# ADC.net
KiCad netlist of a schematic drawn in Altium Designer
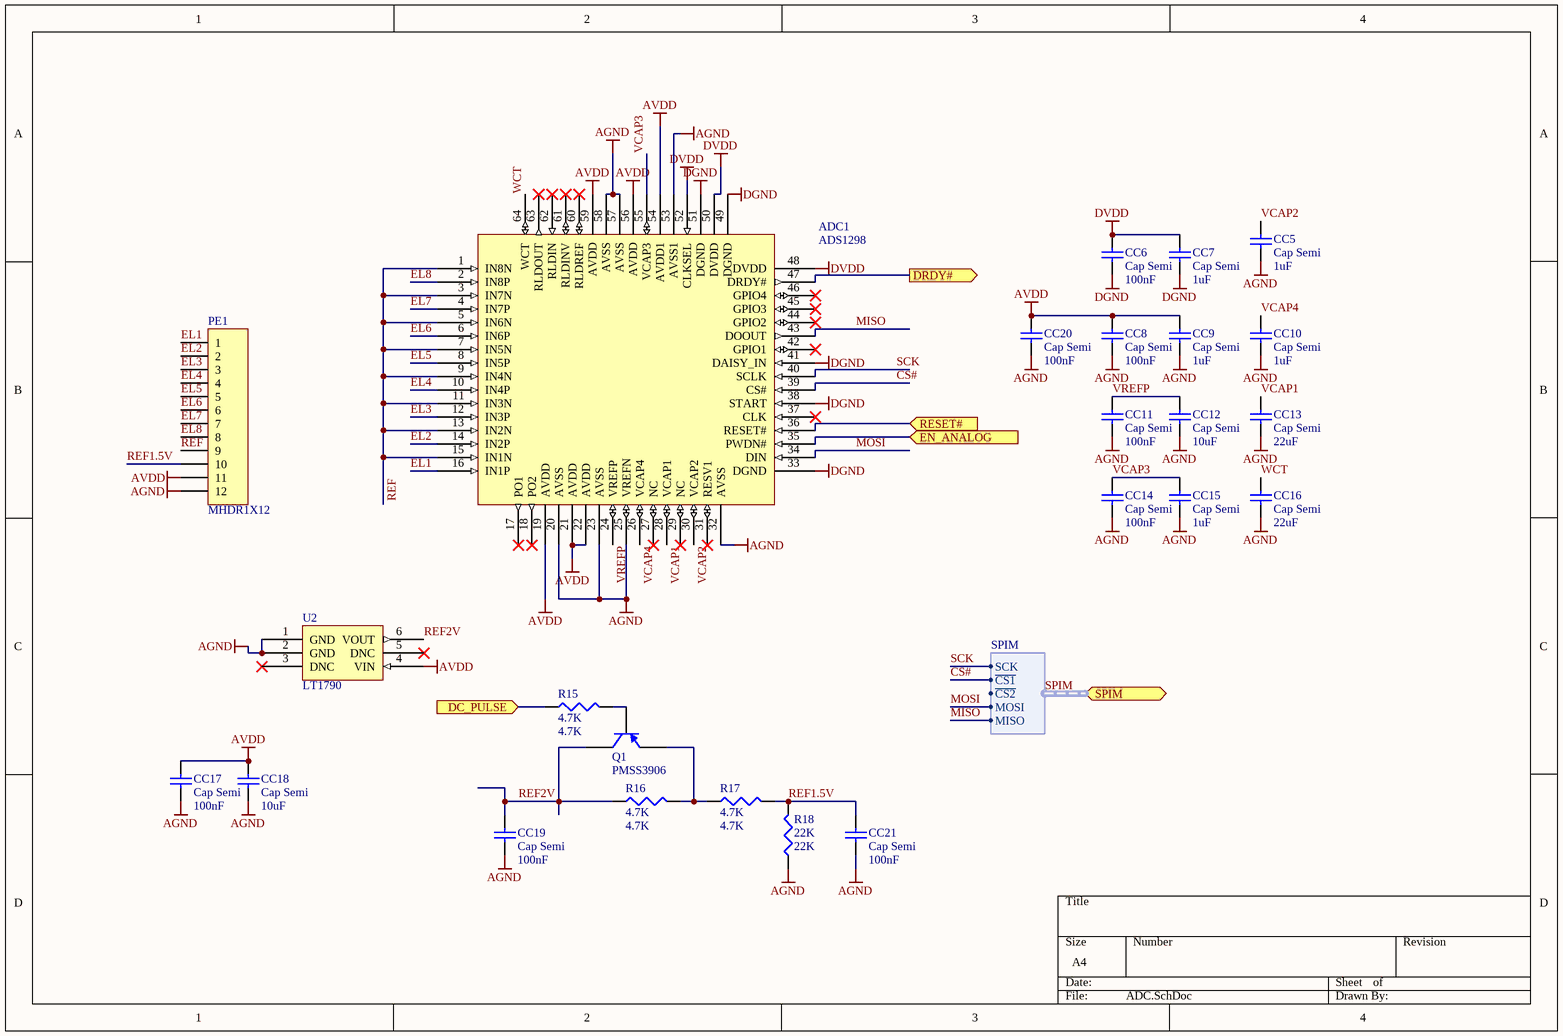
[diagram p0: ADC.SchDoc]

(export (version "E")
  (design (tool "Eeschema 10.0.6"))
  (components
    (comp (ref "ADC1")
      (value "ADS1298")
      (footprint "Atmel Microcontroller 32-Bit ARM:LQFP64_M")
      (libsource (lib "Schlib1") (part "ADS1298"))
    )
    (comp (ref "CC5")
      (value "Cap Semi")
      (footprint "0402")
      (description "Capacitor (Semiconductor SIM Model)")
      (fields (field (name "ALTIUM_VALUE") "1uF") (field (name "PUBLISHER") "Altium Limited"))
      (libsource (lib "Miscellaneous Devices") (part "Cap Semi"))
    )
    (comp (ref "CC6")
      (value "Cap Semi")
      (footprint "0402")
      (description "Capacitor (Semiconductor SIM Model)")
      (fields (field (name "ALTIUM_VALUE") "100nF") (field (name "PUBLISHER") "Altium Limited"))
      (libsource (lib "Miscellaneous Devices") (part "Cap Semi"))
    )
    (comp (ref "CC7")
      (value "Cap Semi")
      (footprint "0402")
      (description "Capacitor (Semiconductor SIM Model)")
      (fields (field (name "ALTIUM_VALUE") "1uF") (field (name "PUBLISHER") "Altium Limited"))
      (libsource (lib "Miscellaneous Devices") (part "Cap Semi"))
    )
    (comp (ref "CC8")
      (value "Cap Semi")
      (footprint "0402")
      (description "Capacitor (Semiconductor SIM Model)")
      (fields (field (name "ALTIUM_VALUE") "100nF") (field (name "PUBLISHER") "Altium Limited"))
      (libsource (lib "Miscellaneous Devices") (part "Cap Semi"))
    )
    (comp (ref "CC9")
      (value "Cap Semi")
      (footprint "0402")
      (description "Capacitor (Semiconductor SIM Model)")
      (fields (field (name "ALTIUM_VALUE") "1uF") (field (name "PUBLISHER") "Altium Limited"))
      (libsource (lib "Miscellaneous Devices") (part "Cap Semi"))
    )
    (comp (ref "CC10")
      (value "Cap Semi")
      (footprint "0402")
      (description "Capacitor (Semiconductor SIM Model)")
      (fields (field (name "ALTIUM_VALUE") "1uF") (field (name "PUBLISHER") "Altium Limited"))
      (libsource (lib "Miscellaneous Devices") (part "Cap Semi"))
    )
    (comp (ref "CC11")
      (value "Cap Semi")
      (footprint "0402")
      (description "Capacitor (Semiconductor SIM Model)")
      (fields (field (name "ALTIUM_VALUE") "100nF") (field (name "PUBLISHER") "Altium Limited"))
      (libsource (lib "Miscellaneous Devices") (part "Cap Semi"))
    )
    (comp (ref "CC12")
      (value "Cap Semi")
      (footprint "0402")
      (description "Capacitor (Semiconductor SIM Model)")
      (fields (field (name "ALTIUM_VALUE") "10uF") (field (name "PUBLISHER") "Altium Limited"))
      (libsource (lib "Miscellaneous Devices") (part "Cap Semi"))
    )
    (comp (ref "CC13")
      (value "Cap Semi")
      (footprint "0402")
      (description "Capacitor (Semiconductor SIM Model)")
      (fields (field (name "ALTIUM_VALUE") "22uF") (field (name "PUBLISHER") "Altium Limited"))
      (libsource (lib "Miscellaneous Devices") (part "Cap Semi"))
    )
    (comp (ref "CC14")
      (value "Cap Semi")
      (footprint "0402")
      (description "Capacitor (Semiconductor SIM Model)")
      (fields (field (name "ALTIUM_VALUE") "100nF") (field (name "PUBLISHER") "Altium Limited"))
      (libsource (lib "Miscellaneous Devices") (part "Cap Semi"))
    )
    (comp (ref "CC15")
      (value "Cap Semi")
      (footprint "0402")
      (description "Capacitor (Semiconductor SIM Model)")
      (fields (field (name "ALTIUM_VALUE") "1uF") (field (name "PUBLISHER") "Altium Limited"))
      (libsource (lib "Miscellaneous Devices") (part "Cap Semi"))
    )
    (comp (ref "CC16")
      (value "Cap Semi")
      (footprint "1608[0603]")
      (description "Capacitor (Semiconductor SIM Model)")
      (fields (field (name "ALTIUM_VALUE") "22uF") (field (name "PUBLISHER") "Altium Limited"))
      (libsource (lib "Miscellaneous Devices") (part "Cap Semi"))
    )
    (comp (ref "CC17")
      (value "Cap Semi")
      (footprint "0402")
      (description "Capacitor (Semiconductor SIM Model)")
      (fields (field (name "ALTIUM_VALUE") "100nF") (field (name "PUBLISHER") "Altium Limited"))
      (libsource (lib "Miscellaneous Devices") (part "Cap Semi"))
    )
    (comp (ref "CC18")
      (value "Cap Semi")
      (footprint "0402")
      (description "Capacitor (Semiconductor SIM Model)")
      (fields (field (name "ALTIUM_VALUE") "10uF") (field (name "PUBLISHER") "Altium Limited"))
      (libsource (lib "Miscellaneous Devices") (part "Cap Semi"))
    )
    (comp (ref "CC19")
      (value "Cap Semi")
      (footprint "0402")
      (description "Capacitor (Semiconductor SIM Model)")
      (fields (field (name "ALTIUM_VALUE") "100nF") (field (name "PUBLISHER") "Altium Limited"))
      (libsource (lib "Miscellaneous Devices") (part "Cap Semi"))
    )
    (comp (ref "CC20")
      (value "Cap Semi")
      (footprint "0402")
      (description "Capacitor (Semiconductor SIM Model)")
      (fields (field (name "ALTIUM_VALUE") "100nF") (field (name "PUBLISHER") "Altium Limited"))
      (libsource (lib "Miscellaneous Devices") (part "Cap Semi"))
    )
    (comp (ref "CC21")
      (value "Cap Semi")
      (footprint "0402")
      (description "Capacitor (Semiconductor SIM Model)")
      (fields (field (name "ALTIUM_VALUE") "100nF") (field (name "PUBLISHER") "Altium Limited"))
      (libsource (lib "Miscellaneous Devices") (part "Cap Semi"))
    )
    (comp (ref "PE1")
      (value "MHDR1X12")
      (footprint "HEADER12")
      (description "Header, 12-Pin")
      (fields (field (name "PUBLISHER") "Altium Limited"))
      (libsource (lib "Miscellaneous Connectors") (part "MHDR1X12"))
    )
    (comp (ref "Q1")
      (value "PMSS3906")
      (footprint "SOT323_N")
      (description "PNP Switching Transistor")
      (fields (field (name "PUBLISHER") "Altium Limited"))
      (libsource (lib "Philips Discrete BJT - Low Power") (part "PMSS3906"))
    )
    (comp (ref "R15")
      (value "4.7K")
      (footprint "0402")
      (description "Resistor")
      (fields (field (name "ALTIUM_VALUE") "4.7K") (field (name "PUBLISHER") "Altium Limited"))
      (libsource (lib "Miscellaneous Devices") (part "Res3"))
    )
    (comp (ref "R16")
      (value "4.7K")
      (footprint "0402")
      (description "Resistor")
      (fields (field (name "ALTIUM_VALUE") "4.7K") (field (name "PUBLISHER") "Altium Limited"))
      (libsource (lib "Miscellaneous Devices") (part "Res3"))
    )
    (comp (ref "R17")
      (value "4.7K")
      (footprint "0402")
      (description "Resistor")
      (fields (field (name "ALTIUM_VALUE") "4.7K") (field (name "PUBLISHER") "Altium Limited"))
      (libsource (lib "Miscellaneous Devices") (part "Res3"))
    )
    (comp (ref "R18")
      (value "22K")
      (footprint "0402")
      (description "Resistor")
      (fields (field (name "ALTIUM_VALUE") "22K") (field (name "PUBLISHER") "Altium Limited"))
      (libsource (lib "Miscellaneous Devices") (part "Res3"))
    )
    (comp (ref "U2") (value "LT1790") (footprint "SOT-23_A_N") (libsource (lib "Schlib1") (part "LT1790")))
  )
  (nets
    (net (code "2") (name "/CS#") (class "Default")
      (node (ref "ADC1") (pin "39") (pinfunction "CS#_39") (pintype "input"))
    )
    (net (code "3") (name "/DC_PULSE") (class "Default")
      (node (ref "R15") (pin "1") (pinfunction "1_1") (pintype "passive"))
    )
    (net (code "4") (name "/DRDY#") (class "Default")
      (node (ref "ADC1") (pin "47") (pinfunction "DRDY#_47") (pintype "output"))
    )
    (net (code "5") (name "/EL1") (class "Default")
      (node (ref "ADC1") (pin "16") (pinfunction "IN1P_16") (pintype "input"))
      (node (ref "PE1") (pin "1") (pinfunction "1_1") (pintype "passive"))
    )
    (net (code "6") (name "/EL2") (class "Default")
      (node (ref "ADC1") (pin "14") (pinfunction "IN2P_14") (pintype "input"))
      (node (ref "PE1") (pin "2") (pinfunction "2_2") (pintype "passive"))
    )
    (net (code "7") (name "/EL3") (class "Default")
      (node (ref "ADC1") (pin "12") (pinfunction "IN3P_12") (pintype "input"))
      (node (ref "PE1") (pin "3") (pinfunction "3_3") (pintype "passive"))
    )
    (net (code "8") (name "/EL4") (class "Default")
      (node (ref "ADC1") (pin "10") (pinfunction "IN4P_10") (pintype "input"))
      (node (ref "PE1") (pin "4") (pinfunction "4_4") (pintype "passive"))
    )
    (net (code "9") (name "/EL5") (class "Default")
      (node (ref "ADC1") (pin "8") (pinfunction "IN5P_8") (pintype "input"))
      (node (ref "PE1") (pin "5") (pinfunction "5_5") (pintype "passive"))
    )
    (net (code "10") (name "/EL6") (class "Default")
      (node (ref "ADC1") (pin "6") (pinfunction "IN6P_6") (pintype "input"))
      (node (ref "PE1") (pin "6") (pinfunction "6_6") (pintype "passive"))
    )
    (net (code "11") (name "/EL7") (class "Default")
      (node (ref "ADC1") (pin "4") (pinfunction "IN7P_4") (pintype "input"))
      (node (ref "PE1") (pin "7") (pinfunction "7_7") (pintype "passive"))
    )
    (net (code "12") (name "/EL8") (class "Default")
      (node (ref "ADC1") (pin "2") (pinfunction "IN8P_2") (pintype "input"))
      (node (ref "PE1") (pin "8") (pinfunction "8_8") (pintype "passive"))
    )
    (net (code "13") (name "/EN_ANALOG") (class "Default")
      (node (ref "ADC1") (pin "35") (pinfunction "PWDN#_35") (pintype "input"))
    )
    (net (code "14") (name "/MISO") (class "Default")
      (node (ref "ADC1") (pin "43") (pinfunction "DOOUT_43") (pintype "output"))
    )
    (net (code "15") (name "/MOSI") (class "Default")
      (node (ref "ADC1") (pin "34") (pinfunction "DIN_34") (pintype "input"))
    )
    (net (code "16") (name "/REF") (class "Default")
      (node (ref "ADC1") (pin "1") (pinfunction "IN8N_1") (pintype "input"))
      (node (ref "ADC1") (pin "11") (pinfunction "IN3N_11") (pintype "input"))
      (node (ref "ADC1") (pin "13") (pinfunction "IN2N_13") (pintype "input"))
      (node (ref "ADC1") (pin "15") (pinfunction "IN1N_15") (pintype "input"))
      (node (ref "ADC1") (pin "3") (pinfunction "IN7N_3") (pintype "input"))
      (node (ref "ADC1") (pin "5") (pinfunction "IN6N_5") (pintype "input"))
      (node (ref "ADC1") (pin "7") (pinfunction "IN5N_7") (pintype "input"))
      (node (ref "ADC1") (pin "9") (pinfunction "IN4N_9") (pintype "input"))
      (node (ref "PE1") (pin "9") (pinfunction "9_9") (pintype "passive"))
    )
    (net (code "17") (name "/REF1.5V") (class "Default")
      (node (ref "CC21") (pin "2") (pinfunction "2_2") (pintype "passive"))
      (node (ref "PE1") (pin "10") (pinfunction "10_10") (pintype "passive"))
      (node (ref "R17") (pin "2") (pinfunction "2_2") (pintype "passive"))
      (node (ref "R18") (pin "2") (pinfunction "2_2") (pintype "passive"))
    )
    (net (code "18") (name "/REF2V") (class "Default")
      (node (ref "CC19") (pin "2") (pinfunction "2_2") (pintype "passive"))
      (node (ref "Q1") (pin "3") (pinfunction "C_3") (pintype "passive"))
      (node (ref "R16") (pin "1") (pinfunction "1_1") (pintype "passive"))
      (node (ref "U2") (pin "6") (pinfunction "VOUT_6") (pintype "output"))
    )
    (net (code "19") (name "/RESET#") (class "Default")
      (node (ref "ADC1") (pin "36") (pinfunction "RESET#_36") (pintype "input"))
    )
    (net (code "20") (name "/SCK") (class "Default")
      (node (ref "ADC1") (pin "40") (pinfunction "SCLK_40") (pintype "input"))
    )
    (net (code "22") (name "/VCAP1") (class "Default")
      (node (ref "ADC1") (pin "28") (pinfunction "VCAP1_28") (pintype "bidirectional"))
      (node (ref "CC13") (pin "2") (pinfunction "2_2") (pintype "passive"))
    )
    (net (code "23") (name "/VCAP2") (class "Default")
      (node (ref "ADC1") (pin "30") (pinfunction "VCAP2_30") (pintype "bidirectional"))
      (node (ref "CC5") (pin "2") (pinfunction "2_2") (pintype "passive"))
    )
    (net (code "24") (name "/VCAP3") (class "Default")
      (node (ref "ADC1") (pin "55") (pinfunction "VCAP3_55") (pintype "bidirectional"))
      (node (ref "CC14") (pin "2") (pinfunction "2_2") (pintype "passive"))
      (node (ref "CC15") (pin "2") (pinfunction "2_2") (pintype "passive"))
    )
    (net (code "25") (name "/VCAP4") (class "Default")
      (node (ref "ADC1") (pin "26") (pinfunction "VCAP4_26") (pintype "bidirectional"))
      (node (ref "CC10") (pin "2") (pinfunction "2_2") (pintype "passive"))
    )
    (net (code "26") (name "/VREFP") (class "Default")
      (node (ref "ADC1") (pin "24") (pinfunction "VREFP_24") (pintype "bidirectional"))
      (node (ref "CC11") (pin "2") (pinfunction "2_2") (pintype "passive"))
      (node (ref "CC12") (pin "2") (pinfunction "2_2") (pintype "passive"))
    )
    (net (code "27") (name "/WCT") (class "Default")
      (node (ref "ADC1") (pin "64") (pinfunction "WCT_64") (pintype "bidirectional"))
      (node (ref "CC16") (pin "2") (pinfunction "2_2") (pintype "passive"))
    )
    (net (code "28") (name "AGND") (class "Default")
      (node (ref "ADC1") (pin "20") (pinfunction "AVSS_20") (pintype "power_in"))
      (node (ref "ADC1") (pin "23") (pinfunction "AVSS_23") (pintype "power_in"))
      (node (ref "ADC1") (pin "25") (pinfunction "VREFN_25") (pintype "bidirectional"))
      (node (ref "ADC1") (pin "32") (pinfunction "AVSS_32") (pintype "power_in"))
      (node (ref "ADC1") (pin "53") (pinfunction "AVSS1_53") (pintype "power_in"))
      (node (ref "ADC1") (pin "57") (pinfunction "AVSS_57") (pintype "power_in"))
      (node (ref "ADC1") (pin "58") (pinfunction "AVSS_58") (pintype "power_in"))
      (node (ref "CC10") (pin "1") (pinfunction "1_1") (pintype "passive"))
      (node (ref "CC11") (pin "1") (pinfunction "1_1") (pintype "passive"))
      (node (ref "CC12") (pin "1") (pinfunction "1_1") (pintype "passive"))
      (node (ref "CC13") (pin "1") (pinfunction "1_1") (pintype "passive"))
      (node (ref "CC14") (pin "1") (pinfunction "1_1") (pintype "passive"))
      (node (ref "CC15") (pin "1") (pinfunction "1_1") (pintype "passive"))
      (node (ref "CC16") (pin "1") (pinfunction "1_1") (pintype "passive"))
      (node (ref "CC17") (pin "1") (pinfunction "1_1") (pintype "passive"))
      (node (ref "CC18") (pin "1") (pinfunction "1_1") (pintype "passive"))
      (node (ref "CC19") (pin "1") (pinfunction "1_1") (pintype "passive"))
      (node (ref "CC20") (pin "1") (pinfunction "1_1") (pintype "passive"))
      (node (ref "CC21") (pin "1") (pinfunction "1_1") (pintype "passive"))
      (node (ref "CC5") (pin "1") (pinfunction "1_1") (pintype "passive"))
      (node (ref "CC8") (pin "1") (pinfunction "1_1") (pintype "passive"))
      (node (ref "CC9") (pin "1") (pinfunction "1_1") (pintype "passive"))
      (node (ref "PE1") (pin "12") (pinfunction "12_12") (pintype "passive"))
      (node (ref "R18") (pin "1") (pinfunction "1_1") (pintype "passive"))
      (node (ref "U2") (pin "1") (pinfunction "GND_1") (pintype "power_in"))
      (node (ref "U2") (pin "2") (pinfunction "GND_2") (pintype "power_in"))
    )
    (net (code "29") (name "AVDD") (class "Default")
      (node (ref "ADC1") (pin "19") (pinfunction "AVDD_19") (pintype "power_in"))
      (node (ref "ADC1") (pin "21") (pinfunction "AVDD_21") (pintype "power_in"))
      (node (ref "ADC1") (pin "22") (pinfunction "AVDD_22") (pintype "power_in"))
      (node (ref "ADC1") (pin "54") (pinfunction "AVDD1_54") (pintype "power_in"))
      (node (ref "ADC1") (pin "56") (pinfunction "AVDD_56") (pintype "power_in"))
      (node (ref "ADC1") (pin "59") (pinfunction "AVDD_59") (pintype "power_in"))
      (node (ref "CC17") (pin "2") (pinfunction "2_2") (pintype "passive"))
      (node (ref "CC18") (pin "2") (pinfunction "2_2") (pintype "passive"))
      (node (ref "CC20") (pin "2") (pinfunction "2_2") (pintype "passive"))
      (node (ref "CC8") (pin "2") (pinfunction "2_2") (pintype "passive"))
      (node (ref "CC9") (pin "2") (pinfunction "2_2") (pintype "passive"))
      (node (ref "PE1") (pin "11") (pinfunction "11_11") (pintype "passive"))
      (node (ref "U2") (pin "4") (pinfunction "VIN_4") (pintype "input"))
    )
    (net (code "30") (name "DGND") (class "Default")
      (node (ref "ADC1") (pin "33") (pinfunction "DGND_33") (pintype "power_in"))
      (node (ref "ADC1") (pin "38") (pinfunction "START_38") (pintype "input"))
      (node (ref "ADC1") (pin "41") (pinfunction "DAISY_IN_41") (pintype "input"))
      (node (ref "ADC1") (pin "49") (pinfunction "DGND_49") (pintype "power_in"))
      (node (ref "ADC1") (pin "51") (pinfunction "DGND_51") (pintype "power_in"))
      (node (ref "CC6") (pin "1") (pinfunction "1_1") (pintype "passive"))
      (node (ref "CC7") (pin "1") (pinfunction "1_1") (pintype "passive"))
    )
    (net (code "31") (name "DVDD") (class "Default")
      (node (ref "ADC1") (pin "48") (pinfunction "DVDD_48") (pintype "power_in"))
      (node (ref "ADC1") (pin "50") (pinfunction "DVDD_50") (pintype "power_in"))
      (node (ref "ADC1") (pin "52") (pinfunction "CLKSEL_52") (pintype "input"))
      (node (ref "CC6") (pin "2") (pinfunction "2_2") (pintype "passive"))
      (node (ref "CC7") (pin "2") (pinfunction "2_2") (pintype "passive"))
    )
    (net (code "32") (name "Net-(Q1-B)") (class "Default")
      (node (ref "Q1") (pin "1") (pinfunction "B_1") (pintype "passive"))
      (node (ref "R15") (pin "2") (pinfunction "2_2") (pintype "passive"))
    )
    (net (code "33") (name "Net-(Q1-E)") (class "Default")
      (node (ref "Q1") (pin "2") (pinfunction "E_2") (pintype "passive"))
      (node (ref "R16") (pin "2") (pinfunction "2_2") (pintype "passive"))
      (node (ref "R17") (pin "1") (pinfunction "1_1") (pintype "passive"))
    )
    (net (code "34") (name "unconnected-(ADC1-CLK-Pad37)") (class "Default")
      (node (ref "ADC1") (pin "37") (pinfunction "CLK_37") (pintype "input+no_connect"))
    )
    (net (code "35") (name "unconnected-(ADC1-GPIO1-Pad42)") (class "Default")
      (node (ref "ADC1") (pin "42") (pinfunction "GPIO1_42") (pintype "bidirectional+no_connect"))
    )
    (net (code "36") (name "unconnected-(ADC1-GPIO2-Pad44)") (class "Default")
      (node (ref "ADC1") (pin "44") (pinfunction "GPIO2_44") (pintype "bidirectional+no_connect"))
    )
    (net (code "37") (name "unconnected-(ADC1-GPIO3-Pad45)") (class "Default")
      (node (ref "ADC1") (pin "45") (pinfunction "GPIO3_45") (pintype "bidirectional+no_connect"))
    )
    (net (code "38") (name "unconnected-(ADC1-GPIO4-Pad46)") (class "Default")
      (node (ref "ADC1") (pin "46") (pinfunction "GPIO4_46") (pintype "bidirectional+no_connect"))
    )
    (net (code "39") (name "unconnected-(ADC1-NC-Pad27)") (class "Default")
      (node (ref "ADC1") (pin "27") (pinfunction "NC_27") (pintype "bidirectional+no_connect"))
    )
    (net (code "40") (name "unconnected-(ADC1-NC-Pad29)") (class "Default")
      (node (ref "ADC1") (pin "29") (pinfunction "NC_29") (pintype "bidirectional+no_connect"))
    )
    (net (code "41") (name "unconnected-(ADC1-PO1-Pad17)") (class "Default")
      (node (ref "ADC1") (pin "17") (pinfunction "PO1_17") (pintype "output+no_connect"))
    )
    (net (code "42") (name "unconnected-(ADC1-PO2-Pad18)") (class "Default")
      (node (ref "ADC1") (pin "18") (pinfunction "PO2_18") (pintype "output+no_connect"))
    )
    (net (code "43") (name "unconnected-(ADC1-RESV1-Pad31)") (class "Default")
      (node (ref "ADC1") (pin "31") (pinfunction "RESV1_31") (pintype "bidirectional+no_connect"))
    )
    (net (code "44") (name "unconnected-(ADC1-RLDIN-Pad62)") (class "Default")
      (node (ref "ADC1") (pin "62") (pinfunction "RLDIN_62") (pintype "input+no_connect"))
    )
    (net (code "45") (name "unconnected-(ADC1-RLDINV-Pad61)") (class "Default")
      (node (ref "ADC1") (pin "61") (pinfunction "RLDINV_61") (pintype "bidirectional+no_connect"))
    )
    (net (code "46") (name "unconnected-(ADC1-RLDOUT-Pad63)") (class "Default")
      (node (ref "ADC1") (pin "63") (pinfunction "RLDOUT_63") (pintype "output+no_connect"))
    )
    (net (code "47") (name "unconnected-(ADC1-RLDREF-Pad60)") (class "Default")
      (node (ref "ADC1") (pin "60") (pinfunction "RLDREF_60") (pintype "bidirectional+no_connect"))
    )
    (net (code "48") (name "unconnected-(U2-DNC-Pad3)") (class "Default")
      (node (ref "U2") (pin "3") (pinfunction "DNC_3") (pintype "passive+no_connect"))
    )
    (net (code "49") (name "unconnected-(U2-DNC-Pad5)") (class "Default")
      (node (ref "U2") (pin "5") (pinfunction "DNC_5") (pintype "passive+no_connect"))
    )
  )
)
